# B35.net
KiCad netlist of a schematic drawn in Altium Designer
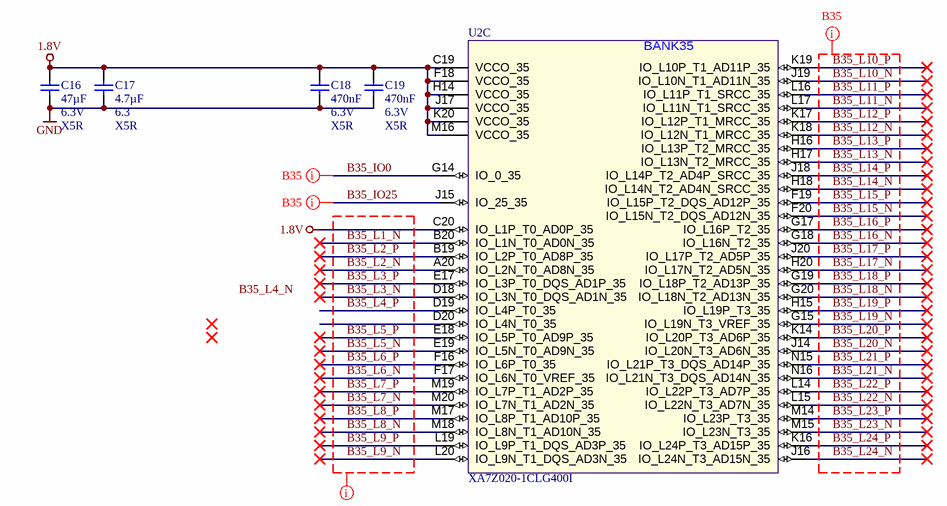
[diagram p0: B35.SchDoc]

(export (version "E")
  (design (tool "Eeschema 10.0.6"))
  (components
    (comp (ref "C16")
      (value "47µF")
      (footprint "CAPC3216X180N")
      (description "KON 47µF 6.3V  X5R SMD 20%")
      (fields
        (field (name "VOLTAGE") "6.3V")
        (field (name "TECHNOLOGY") "X5R")
        (field (name "TOLERANCE") "20%")
      )
      (libsource (lib "TE") (part "CAP-NP"))
    )
    (comp (ref "C17")
      (value "4.7µF")
      (footprint "CAPC1005X60N")
      (description "KON 4.7µF 6.3V X5R SMD")
      (fields (field (name "VOLTAGE") "6.3") (field (name "TECHNOLOGY") "X5R"))
      (libsource (lib "TE") (part "CAP-NP"))
    )
    (comp (ref "C18")
      (value "470nF")
      (footprint "CAPC0603X33N")
      (description "KON 470nF X5R 6.3V SMD")
      (fields
        (field (name "VOLTAGE") "6.3V")
        (field (name "TECHNOLOGY") "X5R")
        (field (name "TOLERANCE") "20%")
      )
      (libsource (lib "TE") (part "CAP-NP"))
    )
    (comp (ref "C19")
      (value "470nF")
      (footprint "CAPC0603X33N")
      (description "KON 470nF X5R 6.3V SMD")
      (fields
        (field (name "VOLTAGE") "6.3V")
        (field (name "TECHNOLOGY") "X5R")
        (field (name "TOLERANCE") "20%")
      )
      (libsource (lib "TE") (part "CAP-NP"))
    )
    (comp (ref "U2")
      (value "XA7Z020-1CLG400I")
      (footprint "BGA400C80P20X20_1700X1700X160N")
      (libsource (lib "TE") (part "XC7Z020-2CLG400C"))
    )
  )
  (nets
    (net (code "1") (name "/B35_IO0") (class "Default")
      (node (ref "U2") (pin "G14") (pinfunction "IO_0_35_G14") (pintype "bidirectional"))
    )
    (net (code "2") (name "/B35_IO25") (class "Default")
      (node (ref "U2") (pin "J15") (pinfunction "IO_25_35_J15") (pintype "bidirectional"))
    )
    (net (code "3") (name "/B35_L1_N") (class "Default")
      (node (ref "U2") (pin "B20") (pinfunction "IO_L1N_T0_AD0N_35_B20") (pintype "bidirectional+no_connect"))
    )
    (net (code "4") (name "/B35_L2_N") (class "Default")
      (node (ref "U2") (pin "A20") (pinfunction "IO_L2N_T0_AD8N_35_A20") (pintype "bidirectional+no_connect"))
    )
    (net (code "5") (name "/B35_L2_P") (class "Default")
      (node (ref "U2") (pin "B19") (pinfunction "IO_L2P_T0_AD8P_35_B19") (pintype "bidirectional+no_connect"))
    )
    (net (code "6") (name "/B35_L3_N") (class "Default")
      (node (ref "U2") (pin "D18") (pinfunction "IO_L3N_T0_DQS_AD1N_35_D18") (pintype "bidirectional+no_connect"))
    )
    (net (code "7") (name "/B35_L3_P") (class "Default")
      (node (ref "U2") (pin "E17") (pinfunction "IO_L3P_T0_DQS_AD1P_35_E17") (pintype "bidirectional+no_connect"))
    )
    (net (code "9") (name "/B35_L4_P") (class "Default")
      (node (ref "U2") (pin "D19") (pinfunction "IO_L4P_T0_35_D19") (pintype "bidirectional"))
    )
    (net (code "10") (name "/B35_L5_N") (class "Default")
      (node (ref "U2") (pin "E19") (pinfunction "IO_L5N_T0_AD9N_35_E19") (pintype "bidirectional+no_connect"))
    )
    (net (code "11") (name "/B35_L5_P") (class "Default")
      (node (ref "U2") (pin "E18") (pinfunction "IO_L5P_T0_AD9P_35_E18") (pintype "bidirectional+no_connect"))
    )
    (net (code "12") (name "/B35_L6_N") (class "Default")
      (node (ref "U2") (pin "F17") (pinfunction "IO_L6N_T0_VREF_35_F17") (pintype "bidirectional+no_connect"))
    )
    (net (code "13") (name "/B35_L6_P") (class "Default")
      (node (ref "U2") (pin "F16") (pinfunction "IO_L6P_T0_35_F16") (pintype "bidirectional+no_connect"))
    )
    (net (code "14") (name "/B35_L7_N") (class "Default")
      (node (ref "U2") (pin "M20") (pinfunction "IO_L7N_T1_AD2N_35_M20") (pintype "bidirectional+no_connect"))
    )
    (net (code "15") (name "/B35_L7_P") (class "Default")
      (node (ref "U2") (pin "M19") (pinfunction "IO_L7P_T1_AD2P_35_M19") (pintype "bidirectional+no_connect"))
    )
    (net (code "16") (name "/B35_L8_N") (class "Default")
      (node (ref "U2") (pin "M18") (pinfunction "IO_L8N_T1_AD10N_35_M18") (pintype "bidirectional+no_connect"))
    )
    (net (code "17") (name "/B35_L8_P") (class "Default")
      (node (ref "U2") (pin "M17") (pinfunction "IO_L8P_T1_AD10P_35_M17") (pintype "bidirectional+no_connect"))
    )
    (net (code "18") (name "/B35_L9_N") (class "Default")
      (node (ref "U2") (pin "L20") (pinfunction "IO_L9N_T1_DQS_AD3N_35_L20") (pintype "bidirectional+no_connect"))
    )
    (net (code "19") (name "/B35_L9_P") (class "Default")
      (node (ref "U2") (pin "L19") (pinfunction "IO_L9P_T1_DQS_AD3P_35_L19") (pintype "bidirectional+no_connect"))
    )
    (net (code "20") (name "/B35_L10_N") (class "Default")
      (node (ref "U2") (pin "J19") (pinfunction "IO_L10N_T1_AD11N_35_J19") (pintype "bidirectional+no_connect"))
    )
    (net (code "21") (name "/B35_L10_P") (class "Default")
      (node (ref "U2") (pin "K19") (pinfunction "IO_L10P_T1_AD11P_35_K19") (pintype "bidirectional+no_connect"))
    )
    (net (code "22") (name "/B35_L11_N") (class "Default")
      (node (ref "U2") (pin "L17") (pinfunction "IO_L11N_T1_SRCC_35_L17") (pintype "bidirectional+no_connect"))
    )
    (net (code "23") (name "/B35_L11_P") (class "Default")
      (node (ref "U2") (pin "L16") (pinfunction "IO_L11P_T1_SRCC_35_L16") (pintype "bidirectional+no_connect"))
    )
    (net (code "24") (name "/B35_L12_N") (class "Default")
      (node (ref "U2") (pin "K18") (pinfunction "IO_L12N_T1_MRCC_35_K18") (pintype "bidirectional+no_connect"))
    )
    (net (code "25") (name "/B35_L12_P") (class "Default")
      (node (ref "U2") (pin "K17") (pinfunction "IO_L12P_T1_MRCC_35_K17") (pintype "bidirectional+no_connect"))
    )
    (net (code "26") (name "/B35_L13_N") (class "Default")
      (node (ref "U2") (pin "H17") (pinfunction "IO_L13N_T2_MRCC_35_H17") (pintype "bidirectional+no_connect"))
    )
    (net (code "27") (name "/B35_L13_P") (class "Default")
      (node (ref "U2") (pin "H16") (pinfunction "IO_L13P_T2_MRCC_35_H16") (pintype "bidirectional+no_connect"))
    )
    (net (code "28") (name "/B35_L14_N") (class "Default")
      (node (ref "U2") (pin "H18") (pinfunction "IO_L14N_T2_AD4N_SRCC_35_H18") (pintype "bidirectional+no_connect"))
    )
    (net (code "29") (name "/B35_L14_P") (class "Default")
      (node (ref "U2") (pin "J18") (pinfunction "IO_L14P_T2_AD4P_SRCC_35_J18") (pintype "bidirectional+no_connect"))
    )
    (net (code "30") (name "/B35_L15_N") (class "Default")
      (node (ref "U2") (pin "F20") (pinfunction "IO_L15N_T2_DQS_AD12N_35_F20") (pintype "bidirectional+no_connect"))
    )
    (net (code "31") (name "/B35_L15_P") (class "Default")
      (node (ref "U2") (pin "F19") (pinfunction "IO_L15P_T2_DQS_AD12P_35_F19") (pintype "bidirectional+no_connect"))
    )
    (net (code "32") (name "/B35_L16_N") (class "Default")
      (node (ref "U2") (pin "G18") (pinfunction "IO_L16N_T2_35_G18") (pintype "bidirectional+no_connect"))
    )
    (net (code "33") (name "/B35_L16_P") (class "Default")
      (node (ref "U2") (pin "G17") (pinfunction "IO_L16P_T2_35_G17") (pintype "bidirectional+no_connect"))
    )
    (net (code "34") (name "/B35_L17_N") (class "Default")
      (node (ref "U2") (pin "H20") (pinfunction "IO_L17N_T2_AD5N_35_H20") (pintype "bidirectional+no_connect"))
    )
    (net (code "35") (name "/B35_L17_P") (class "Default")
      (node (ref "U2") (pin "J20") (pinfunction "IO_L17P_T2_AD5P_35_J20") (pintype "bidirectional+no_connect"))
    )
    (net (code "36") (name "/B35_L18_N") (class "Default")
      (node (ref "U2") (pin "G20") (pinfunction "IO_L18N_T2_AD13N_35_G20") (pintype "bidirectional+no_connect"))
    )
    (net (code "37") (name "/B35_L18_P") (class "Default")
      (node (ref "U2") (pin "G19") (pinfunction "IO_L18P_T2_AD13P_35_G19") (pintype "bidirectional+no_connect"))
    )
    (net (code "38") (name "/B35_L19_N") (class "Default")
      (node (ref "U2") (pin "G15") (pinfunction "IO_L19N_T3_VREF_35_G15") (pintype "bidirectional+no_connect"))
    )
    (net (code "39") (name "/B35_L19_P") (class "Default")
      (node (ref "U2") (pin "H15") (pinfunction "IO_L19P_T3_35_H15") (pintype "bidirectional+no_connect"))
    )
    (net (code "40") (name "/B35_L20_N") (class "Default")
      (node (ref "U2") (pin "J14") (pinfunction "IO_L20N_T3_AD6N_35_J14") (pintype "bidirectional+no_connect"))
    )
    (net (code "41") (name "/B35_L20_P") (class "Default")
      (node (ref "U2") (pin "K14") (pinfunction "IO_L20P_T3_AD6P_35_K14") (pintype "bidirectional+no_connect"))
    )
    (net (code "42") (name "/B35_L21_N") (class "Default")
      (node (ref "U2") (pin "N16") (pinfunction "IO_L21N_T3_DQS_AD14N_35_N16") (pintype "bidirectional+no_connect"))
    )
    (net (code "43") (name "/B35_L21_P") (class "Default")
      (node (ref "U2") (pin "N15") (pinfunction "IO_L21P_T3_DQS_AD14P_35_N15") (pintype "bidirectional+no_connect"))
    )
    (net (code "44") (name "/B35_L22_N") (class "Default")
      (node (ref "U2") (pin "L15") (pinfunction "IO_L22N_T3_AD7N_35_L15") (pintype "bidirectional+no_connect"))
    )
    (net (code "45") (name "/B35_L22_P") (class "Default")
      (node (ref "U2") (pin "L14") (pinfunction "IO_L22P_T3_AD7P_35_L14") (pintype "bidirectional+no_connect"))
    )
    (net (code "46") (name "/B35_L23_N") (class "Default")
      (node (ref "U2") (pin "M15") (pinfunction "IO_L23N_T3_35_M15") (pintype "bidirectional+no_connect"))
    )
    (net (code "47") (name "/B35_L23_P") (class "Default")
      (node (ref "U2") (pin "M14") (pinfunction "IO_L23P_T3_35_M14") (pintype "bidirectional+no_connect"))
    )
    (net (code "48") (name "/B35_L24_N") (class "Default")
      (node (ref "U2") (pin "J16") (pinfunction "IO_L24N_T3_AD15N_35_J16") (pintype "bidirectional+no_connect"))
    )
    (net (code "49") (name "/B35_L24_P") (class "Default")
      (node (ref "U2") (pin "K16") (pinfunction "IO_L24P_T3_AD15P_35_K16") (pintype "bidirectional+no_connect"))
    )
    (net (code "50") (name "1.8V") (class "Default")
      (node (ref "C16") (pin "1") (pinfunction "1_1") (pintype "passive"))
      (node (ref "C17") (pin "1") (pinfunction "1_1") (pintype "passive"))
      (node (ref "C18") (pin "1") (pinfunction "1_1") (pintype "passive"))
      (node (ref "C19") (pin "1") (pinfunction "1_1") (pintype "passive"))
      (node (ref "U2") (pin "C19") (pinfunction "VCCO_35_C19") (pintype "power_in"))
      (node (ref "U2") (pin "C20") (pinfunction "IO_L1P_T0_AD0P_35_C20") (pintype "bidirectional"))
      (node (ref "U2") (pin "F18") (pinfunction "VCCO_35_F18") (pintype "power_in"))
      (node (ref "U2") (pin "H14") (pinfunction "VCCO_35_H14") (pintype "power_in"))
      (node (ref "U2") (pin "J17") (pinfunction "VCCO_35_J17") (pintype "power_in"))
      (node (ref "U2") (pin "K20") (pinfunction "VCCO_35_K20") (pintype "power_in"))
      (node (ref "U2") (pin "M16") (pinfunction "VCCO_35_M16") (pintype "power_in"))
    )
    (net (code "51") (name "GND") (class "Default")
      (node (ref "C16") (pin "2") (pinfunction "2_2") (pintype "passive"))
      (node (ref "C17") (pin "2") (pinfunction "2_2") (pintype "passive"))
      (node (ref "C18") (pin "2") (pinfunction "2_2") (pintype "passive"))
      (node (ref "C19") (pin "2") (pinfunction "2_2") (pintype "passive"))
    )
    (net (code "52") (name "unconnected-(U2C-IO_L4N_T0_35-PadD20)") (class "Default")
      (node (ref "U2") (pin "D20") (pinfunction "IO_L4N_T0_35_D20") (pintype "bidirectional"))
    )
  )
)
